# QiCharger.net
KiCad netlist of a schematic drawn in Altium Designer
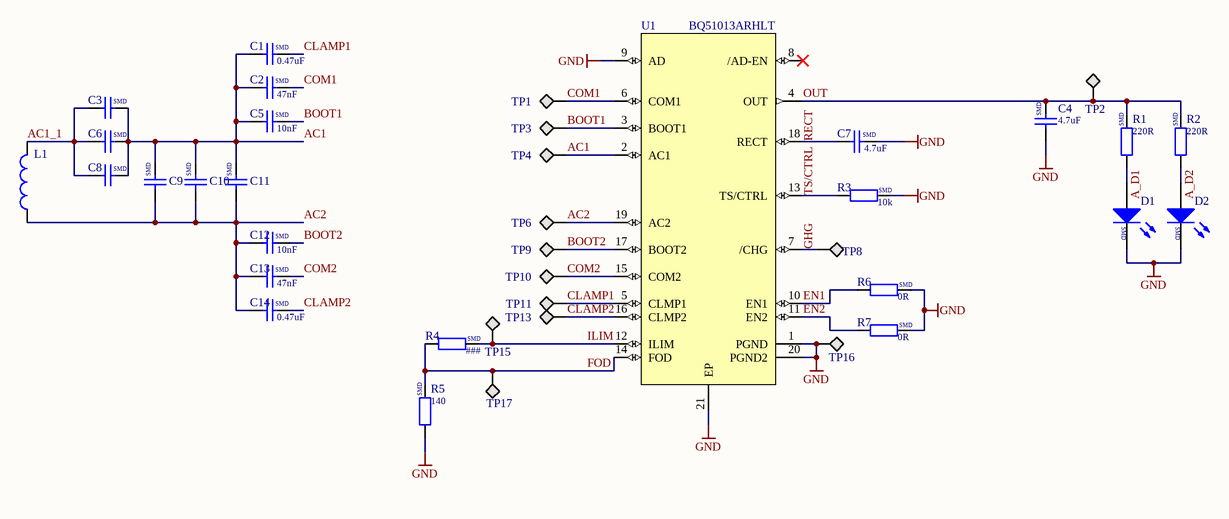
[diagram p0: QiCharger.SchDoc]

(export (version "E")
  (design (tool "Eeschema 10.0.6"))
  (components
    (comp (ref "C1")
      (value "0.47uF")
      (footprint "C_SMD_C0402")
      (description "SMD Capacitor")
      (libsource (lib "HTLInn_RLCQ") (part "C_SMD"))
    )
    (comp (ref "C2")
      (value "47nF")
      (footprint "C_SMD_C0402")
      (description "SMD Capacitor")
      (libsource (lib "HTLInn_RLCQ") (part "C_SMD"))
    )
    (comp (ref "C3")
      (value "###")
      (footprint "C_SMD_C0402")
      (description "SMD Capacitor")
      (libsource (lib "HTLInn_RLCQ") (part "C_SMD"))
    )
    (comp (ref "C4")
      (value "4.7uF")
      (footprint "C_SMD_C0402")
      (description "SMD Capacitor")
      (libsource (lib "HTLInn_RLCQ") (part "C_SMD"))
    )
    (comp (ref "C5")
      (value "10nF")
      (footprint "C_SMD_C0402")
      (description "SMD Capacitor")
      (libsource (lib "HTLInn_RLCQ") (part "C_SMD"))
    )
    (comp (ref "C6")
      (value "###")
      (footprint "C_SMD_C0603")
      (description "SMD Capacitor")
      (libsource (lib "HTLInn_RLCQ") (part "C_SMD"))
    )
    (comp (ref "C7")
      (value "4.7uF")
      (footprint "C_SMD_C0402")
      (description "SMD Capacitor")
      (libsource (lib "HTLInn_RLCQ") (part "C_SMD"))
    )
    (comp (ref "C8")
      (value "###")
      (footprint "C_SMD_C0805")
      (description "SMD Capacitor")
      (libsource (lib "HTLInn_RLCQ") (part "C_SMD"))
    )
    (comp (ref "C9")
      (value "###")
      (footprint "C_SMD_C0805")
      (description "SMD Capacitor")
      (libsource (lib "HTLInn_RLCQ") (part "C_SMD"))
    )
    (comp (ref "C10")
      (value "###")
      (footprint "C_SMD_C0603")
      (description "SMD Capacitor")
      (libsource (lib "HTLInn_RLCQ") (part "C_SMD"))
    )
    (comp (ref "C11")
      (value "###")
      (footprint "C_SMD_C0402")
      (description "SMD Capacitor")
      (libsource (lib "HTLInn_RLCQ") (part "C_SMD"))
    )
    (comp (ref "C12")
      (value "10nF")
      (footprint "C_SMD_C0402")
      (description "SMD Capacitor")
      (libsource (lib "HTLInn_RLCQ") (part "C_SMD"))
    )
    (comp (ref "C13")
      (value "47nF")
      (footprint "C_SMD_C0402")
      (description "SMD Capacitor")
      (libsource (lib "HTLInn_RLCQ") (part "C_SMD"))
    )
    (comp (ref "C14")
      (value "0.47uF")
      (footprint "C_SMD_C0402")
      (description "SMD Capacitor")
      (libsource (lib "HTLInn_RLCQ") (part "C_SMD"))
    )
    (comp (ref "D1")
      (value "SMD LED RED")
      (footprint "SMD_0805_CHIP-LED")
      (description "Red GaAs LED (Vf=1.7V, If=40mA)")
      (libsource (lib "HTLinn_Opto") (part "SMD_LED_RED"))
    )
    (comp (ref "D2")
      (value "SMD LED RED")
      (footprint "SMD_0805_CHIP-LED")
      (description "Red GaAs LED (Vf=1.7V, If=40mA)")
      (libsource (lib "HTLinn_Opto") (part "SMD_LED_RED"))
    )
    (comp (ref "L1")
      (value "Trace Coil")
      (footprint "PCBComponent_1")
      (description "roughly 4uH; trace width of 0.4mm")
      (libsource (lib "TraceCoil") (part "Trace Coil"))
    )
    (comp (ref "R1")
      (value "220R")
      (footprint "R_SMD_R0402")
      (description "SMD Resistor")
      (libsource (lib "HTLInn_RLCQ") (part "R_SMD"))
    )
    (comp (ref "R2")
      (value "220R")
      (footprint "R_SMD_R0402")
      (description "SMD Resistor")
      (libsource (lib "HTLInn_RLCQ") (part "R_SMD"))
    )
    (comp (ref "R3")
      (value "10k")
      (footprint "R_SMD_R0402")
      (description "SMD Resistor")
      (libsource (lib "") (part "R_SMD_1"))
    )
    (comp (ref "R4")
      (value "###")
      (footprint "R_SMD_R0402")
      (description "SMD Resistor")
      (libsource (lib "") (part "R_SMD_1"))
    )
    (comp (ref "R5")
      (value "140")
      (footprint "R_SMD_R0402")
      (description "SMD Resistor")
      (libsource (lib "HTLInn_RLCQ") (part "R_SMD"))
    )
    (comp (ref "R6")
      (value "0R")
      (footprint "R_SMD_R0402")
      (description "SMD Resistor")
      (libsource (lib "") (part "R_SMD_1"))
    )
    (comp (ref "R7")
      (value "0R")
      (footprint "R_SMD_R0402")
      (description "SMD Resistor")
      (libsource (lib "") (part "R_SMD_1"))
    )
    (comp (ref "TP1")
      (value "TESTPOINT")
      (footprint "TP_1.25MM")
      (description "Test Point")
      (fields (field (name "PUBLISHER") "Michael Kupfner"))
      (libsource (lib "myUSB_Schtick") (part "TP TEST POINT"))
    )
    (comp (ref "TP2")
      (value "TESTPOINT")
      (footprint "TP_1.25MM")
      (description "Test Point")
      (fields (field (name "PUBLISHER") "Michael Kupfner"))
      (libsource (lib "myUSB_Schtick") (part "TP TEST POINT"))
    )
    (comp (ref "TP3")
      (value "TESTPOINT")
      (footprint "TP_1.25MM")
      (description "Test Point")
      (fields (field (name "PUBLISHER") "Michael Kupfner"))
      (libsource (lib "myUSB_Schtick") (part "TP TEST POINT"))
    )
    (comp (ref "TP4")
      (value "TESTPOINT")
      (footprint "TP_1.25MM")
      (description "Test Point")
      (fields (field (name "PUBLISHER") "Michael Kupfner"))
      (libsource (lib "myUSB_Schtick") (part "TP TEST POINT"))
    )
    (comp (ref "TP6")
      (value "TESTPOINT")
      (footprint "TP_1.25MM")
      (description "Test Point")
      (fields (field (name "PUBLISHER") "Michael Kupfner"))
      (libsource (lib "myUSB_Schtick") (part "TP TEST POINT"))
    )
    (comp (ref "TP8")
      (value "TESTPOINT")
      (footprint "TP_1.25MM")
      (description "Test Point")
      (fields (field (name "PUBLISHER") "Michael Kupfner"))
      (libsource (lib "myUSB_Schtick") (part "TP TEST POINT"))
    )
    (comp (ref "TP9")
      (value "TESTPOINT")
      (footprint "TP_1.25MM")
      (description "Test Point")
      (fields (field (name "PUBLISHER") "Michael Kupfner"))
      (libsource (lib "myUSB_Schtick") (part "TP TEST POINT"))
    )
    (comp (ref "TP10")
      (value "TESTPOINT")
      (footprint "TP_1.25MM")
      (description "Test Point")
      (fields (field (name "PUBLISHER") "Michael Kupfner"))
      (libsource (lib "myUSB_Schtick") (part "TP TEST POINT"))
    )
    (comp (ref "TP11")
      (value "TESTPOINT")
      (footprint "TP_1.25MM")
      (description "Test Point")
      (fields (field (name "PUBLISHER") "Michael Kupfner"))
      (libsource (lib "myUSB_Schtick") (part "TP TEST POINT"))
    )
    (comp (ref "TP13")
      (value "TESTPOINT")
      (footprint "TP_1.25MM")
      (description "Test Point")
      (fields (field (name "PUBLISHER") "Michael Kupfner"))
      (libsource (lib "myUSB_Schtick") (part "TP TEST POINT"))
    )
    (comp (ref "TP15")
      (value "TESTPOINT")
      (footprint "TP_1.25MM")
      (description "Test Point")
      (fields (field (name "PUBLISHER") "Michael Kupfner"))
      (libsource (lib "myUSB_Schtick") (part "TP TEST POINT"))
    )
    (comp (ref "TP16")
      (value "TESTPOINT")
      (footprint "TP_1.25MM")
      (description "Test Point")
      (fields (field (name "PUBLISHER") "Michael Kupfner"))
      (libsource (lib "myUSB_Schtick") (part "TP TEST POINT"))
    )
    (comp (ref "TP17")
      (value "TESTPOINT")
      (footprint "TP_1.25MM")
      (description "Test Point")
      (fields (field (name "PUBLISHER") "Michael Kupfner"))
      (libsource (lib "myUSB_Schtick") (part "TP TEST POINT"))
    )
    (comp (ref "U1")
      (value "BQ51013ARHLT")
      (footprint "IC_MSP430FR2522IRHLR")
      (fields (field (name "MF") "Texas Instruments"))
      (libsource (lib "BQ51013ARHLT") (part "BQ51013ARHLT"))
    )
  )
  (nets
    (net (code "1") (name "/AC1") (class "Default")
      (node (ref "C1") (pin "1") (pinfunction "1_1") (pintype "passive"))
      (node (ref "C10") (pin "2") (pinfunction "2_2") (pintype "passive"))
      (node (ref "C11") (pin "2") (pinfunction "2_2") (pintype "passive"))
      (node (ref "C2") (pin "1") (pinfunction "1_1") (pintype "passive"))
      (node (ref "C3") (pin "2") (pinfunction "2_2") (pintype "passive"))
      (node (ref "C5") (pin "1") (pinfunction "1_1") (pintype "passive"))
      (node (ref "C6") (pin "2") (pinfunction "2_2") (pintype "passive"))
      (node (ref "C8") (pin "2") (pinfunction "2_2") (pintype "passive"))
      (node (ref "C9") (pin "2") (pinfunction "2_2") (pintype "passive"))
      (node (ref "TP4") (pin "1") (pinfunction "1_1") (pintype "passive"))
      (node (ref "U1") (pin "2") (pinfunction "AC1_2") (pintype "bidirectional"))
    )
    (net (code "2") (name "/AC1_1") (class "Default")
      (node (ref "C3") (pin "1") (pinfunction "1_1") (pintype "passive"))
      (node (ref "C6") (pin "1") (pinfunction "1_1") (pintype "passive"))
      (node (ref "C8") (pin "1") (pinfunction "1_1") (pintype "passive"))
      (node (ref "L1") (pin "1") (pinfunction "1_1") (pintype "passive"))
    )
    (net (code "3") (name "/AC2") (class "Default")
      (node (ref "C10") (pin "1") (pinfunction "1_1") (pintype "passive"))
      (node (ref "C11") (pin "1") (pinfunction "1_1") (pintype "passive"))
      (node (ref "C12") (pin "1") (pinfunction "1_1") (pintype "passive"))
      (node (ref "C13") (pin "1") (pinfunction "1_1") (pintype "passive"))
      (node (ref "C14") (pin "1") (pinfunction "1_1") (pintype "passive"))
      (node (ref "C9") (pin "1") (pinfunction "1_1") (pintype "passive"))
      (node (ref "L1") (pin "2") (pinfunction "2_2") (pintype "passive"))
      (node (ref "TP6") (pin "1") (pinfunction "1_1") (pintype "passive"))
      (node (ref "U1") (pin "19") (pinfunction "AC2_19") (pintype "bidirectional"))
    )
    (net (code "4") (name "/A_D1") (class "Default")
      (node (ref "D1") (pin "A") (pinfunction "A_A") (pintype "passive"))
      (node (ref "R1") (pin "1") (pinfunction "1_1") (pintype "passive"))
    )
    (net (code "5") (name "/A_D2") (class "Default")
      (node (ref "D2") (pin "A") (pinfunction "A_A") (pintype "passive"))
      (node (ref "R2") (pin "1") (pinfunction "1_1") (pintype "passive"))
    )
    (net (code "6") (name "/BOOT1") (class "Default")
      (node (ref "C5") (pin "2") (pinfunction "2_2") (pintype "passive"))
      (node (ref "TP3") (pin "1") (pinfunction "1_1") (pintype "passive"))
      (node (ref "U1") (pin "3") (pinfunction "BOOT1_3") (pintype "bidirectional"))
    )
    (net (code "7") (name "/BOOT2") (class "Default")
      (node (ref "C12") (pin "2") (pinfunction "2_2") (pintype "passive"))
      (node (ref "TP9") (pin "1") (pinfunction "1_1") (pintype "passive"))
      (node (ref "U1") (pin "17") (pinfunction "BOOT2_17") (pintype "bidirectional"))
    )
    (net (code "8") (name "/CLAMP1") (class "Default")
      (node (ref "C1") (pin "2") (pinfunction "2_2") (pintype "passive"))
      (node (ref "TP11") (pin "1") (pinfunction "1_1") (pintype "passive"))
      (node (ref "U1") (pin "5") (pinfunction "CLMP1_5") (pintype "bidirectional"))
    )
    (net (code "9") (name "/CLAMP2") (class "Default")
      (node (ref "C14") (pin "2") (pinfunction "2_2") (pintype "passive"))
      (node (ref "TP13") (pin "1") (pinfunction "1_1") (pintype "passive"))
      (node (ref "U1") (pin "16") (pinfunction "CLMP2_16") (pintype "bidirectional"))
    )
    (net (code "10") (name "/COM1") (class "Default")
      (node (ref "C2") (pin "2") (pinfunction "2_2") (pintype "passive"))
      (node (ref "TP1") (pin "1") (pinfunction "1_1") (pintype "passive"))
      (node (ref "U1") (pin "6") (pinfunction "COM1_6") (pintype "bidirectional"))
    )
    (net (code "11") (name "/COM2") (class "Default")
      (node (ref "C13") (pin "2") (pinfunction "2_2") (pintype "passive"))
      (node (ref "TP10") (pin "1") (pinfunction "1_1") (pintype "passive"))
      (node (ref "U1") (pin "15") (pinfunction "COM2_15") (pintype "bidirectional"))
    )
    (net (code "12") (name "/EN1") (class "Default")
      (node (ref "R6") (pin "1") (pinfunction "1_1") (pintype "passive"))
      (node (ref "U1") (pin "10") (pinfunction "EN1_10") (pintype "bidirectional"))
    )
    (net (code "13") (name "/EN2") (class "Default")
      (node (ref "R7") (pin "1") (pinfunction "1_1") (pintype "passive"))
      (node (ref "U1") (pin "11") (pinfunction "EN2_11") (pintype "bidirectional"))
    )
    (net (code "14") (name "/FOD") (class "Default")
      (node (ref "R4") (pin "1") (pinfunction "1_1") (pintype "passive"))
      (node (ref "R5") (pin "2") (pinfunction "2_2") (pintype "passive"))
      (node (ref "TP17") (pin "1") (pinfunction "1_1") (pintype "passive"))
      (node (ref "U1") (pin "14") (pinfunction "FOD_14") (pintype "bidirectional"))
    )
    (net (code "15") (name "/GHG") (class "Default")
      (node (ref "TP8") (pin "1") (pinfunction "1_1") (pintype "passive"))
      (node (ref "U1") (pin "7") (pinfunction "/CHG_7") (pintype "bidirectional"))
    )
    (net (code "16") (name "/ILIM") (class "Default")
      (node (ref "R4") (pin "2") (pinfunction "2_2") (pintype "passive"))
      (node (ref "TP15") (pin "1") (pinfunction "1_1") (pintype "passive"))
      (node (ref "U1") (pin "12") (pinfunction "ILIM_12") (pintype "bidirectional"))
    )
    (net (code "17") (name "/OUT") (class "Default")
      (node (ref "C4") (pin "2") (pinfunction "2_2") (pintype "passive"))
      (node (ref "R1") (pin "2") (pinfunction "2_2") (pintype "passive"))
      (node (ref "R2") (pin "2") (pinfunction "2_2") (pintype "passive"))
      (node (ref "TP2") (pin "1") (pinfunction "1_1") (pintype "passive"))
      (node (ref "U1") (pin "4") (pinfunction "OUT_4") (pintype "output"))
    )
    (net (code "18") (name "/RECT") (class "Default")
      (node (ref "C7") (pin "1") (pinfunction "1_1") (pintype "passive"))
      (node (ref "U1") (pin "18") (pinfunction "RECT_18") (pintype "bidirectional"))
    )
    (net (code "19") (name "/TS{slash}CTRL") (class "Default")
      (node (ref "R3") (pin "1") (pinfunction "1_1") (pintype "passive"))
      (node (ref "U1") (pin "13") (pinfunction "TS/CTRL_13") (pintype "bidirectional"))
    )
    (net (code "20") (name "GND") (class "Default")
      (node (ref "C4") (pin "1") (pinfunction "1_1") (pintype "passive"))
      (node (ref "C7") (pin "2") (pinfunction "2_2") (pintype "passive"))
      (node (ref "D1") (pin "K") (pinfunction "K_K") (pintype "passive"))
      (node (ref "D2") (pin "K") (pinfunction "K_K") (pintype "passive"))
      (node (ref "R3") (pin "2") (pinfunction "2_2") (pintype "passive"))
      (node (ref "R5") (pin "1") (pinfunction "1_1") (pintype "passive"))
      (node (ref "R6") (pin "2") (pinfunction "2_2") (pintype "passive"))
      (node (ref "R7") (pin "2") (pinfunction "2_2") (pintype "passive"))
      (node (ref "TP16") (pin "1") (pinfunction "1_1") (pintype "passive"))
      (node (ref "U1") (pin "1") (pinfunction "PGND_1") (pintype "power_in"))
      (node (ref "U1") (pin "20") (pinfunction "PGND2_20") (pintype "power_in"))
      (node (ref "U1") (pin "21") (pinfunction "EP_21") (pintype "power_in"))
      (node (ref "U1") (pin "9") (pinfunction "AD_9") (pintype "bidirectional"))
    )
    (net (code "21") (name "unconnected-(U1-{slash}AD-EN-Pad8)") (class "Default")
      (node (ref "U1") (pin "8") (pinfunction "/AD-EN_8") (pintype "bidirectional+no_connect"))
    )
  )
)
